# HMI_Features.net
KiCad netlist of a schematic drawn in Altium Designer
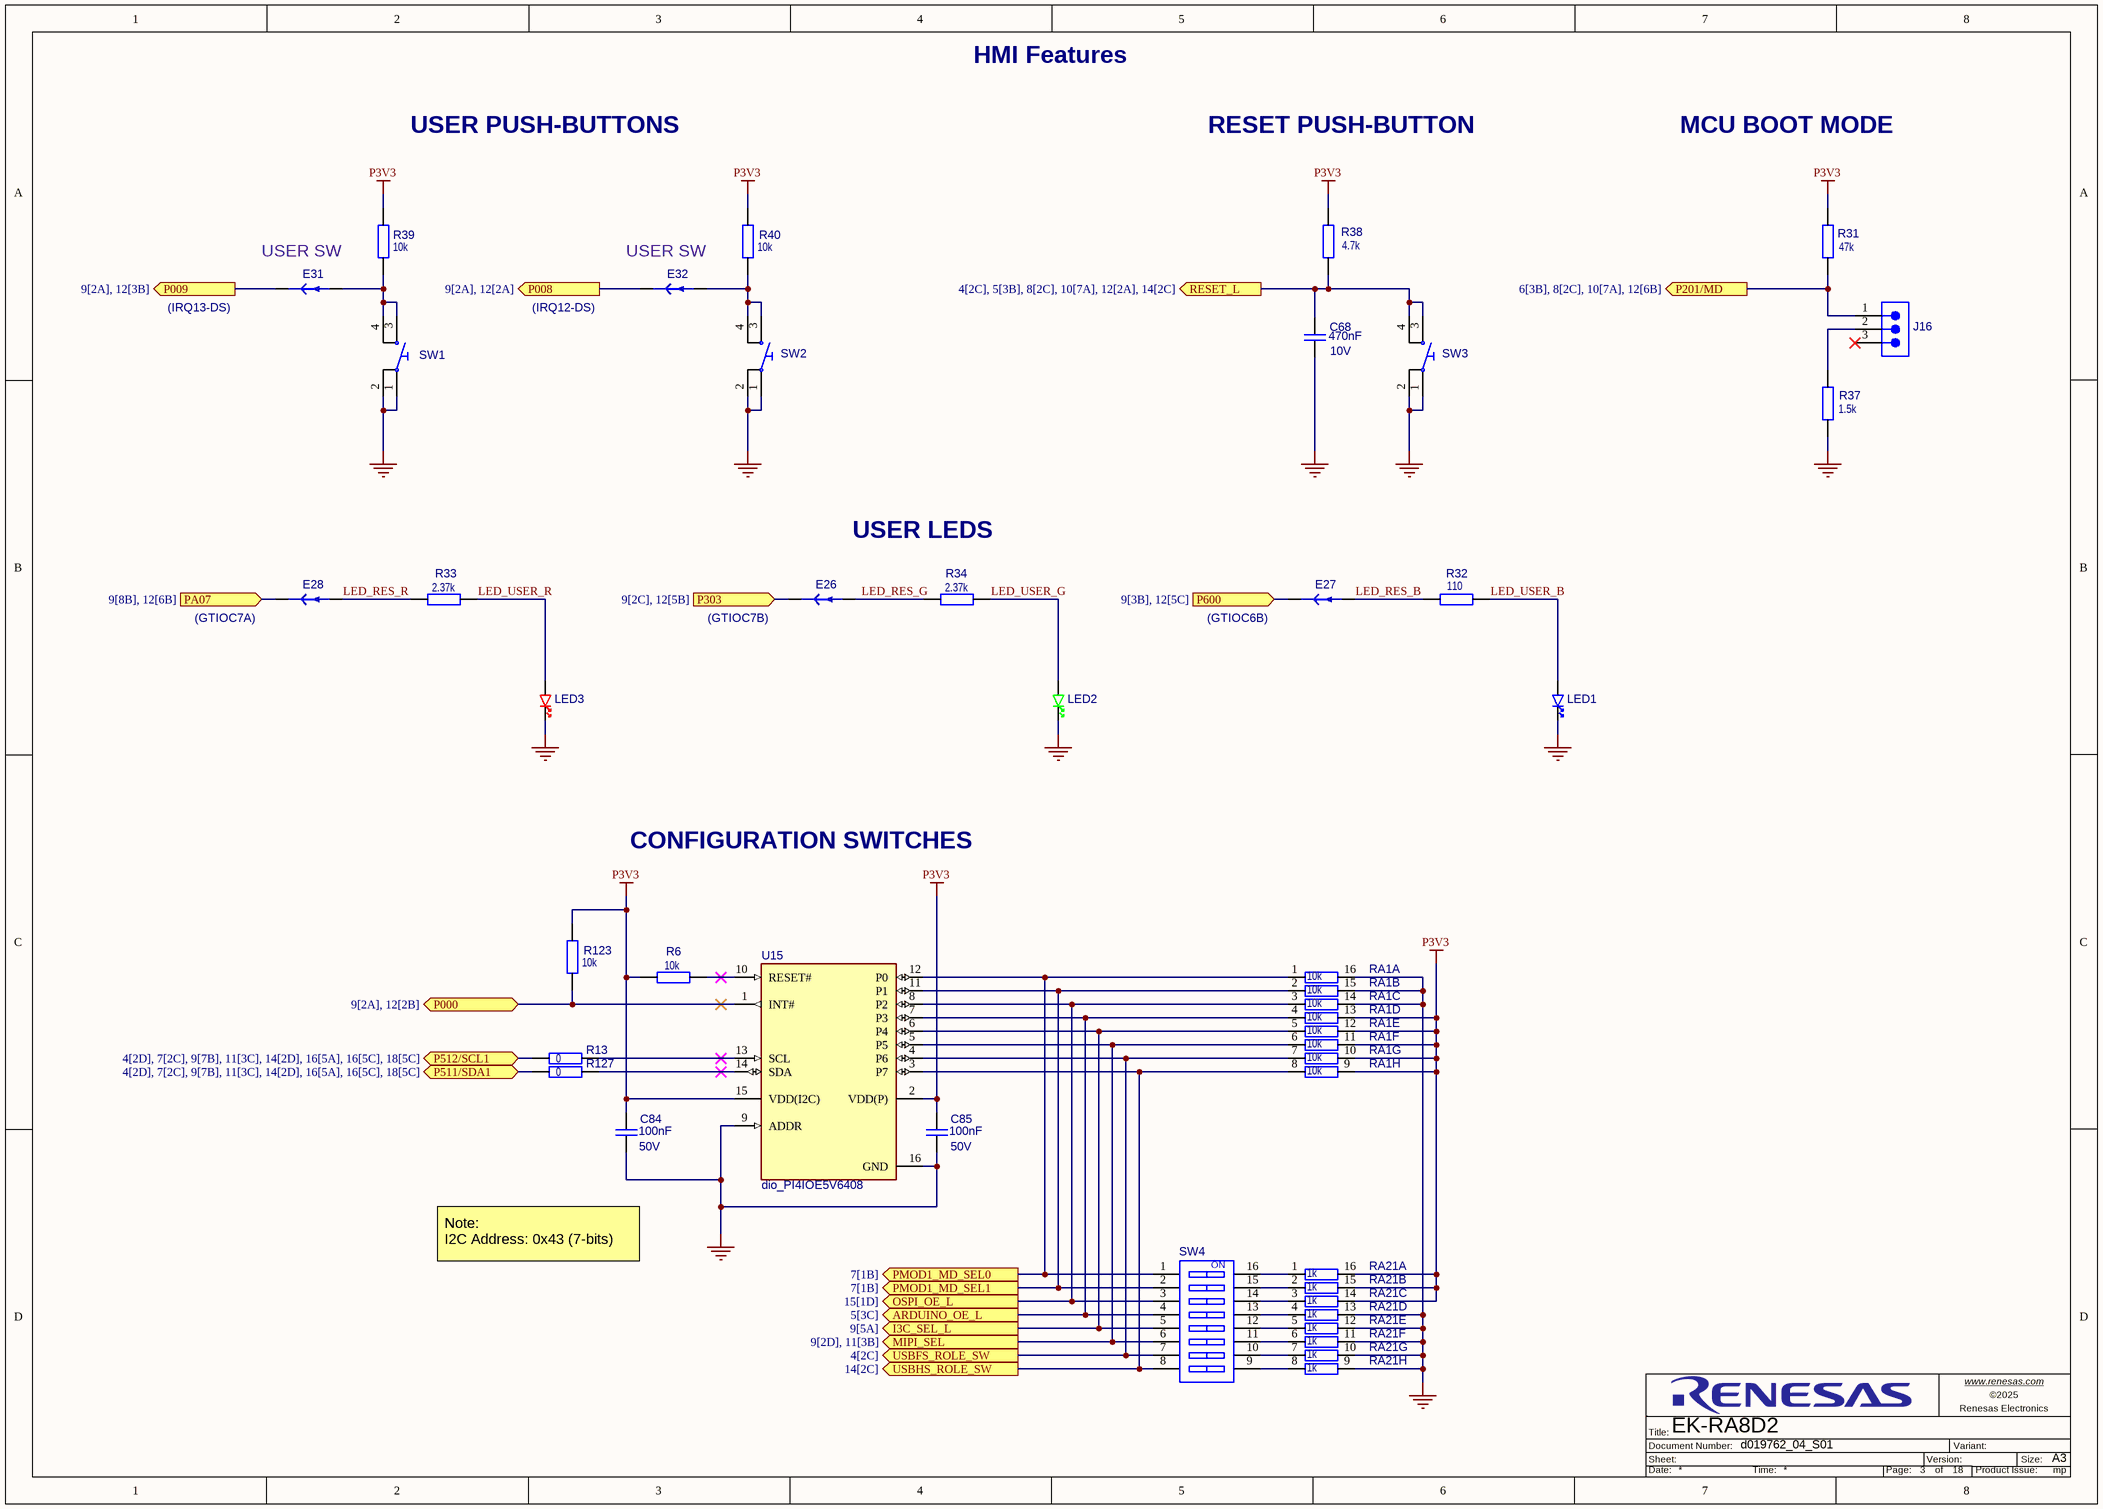
[diagram p0: HMI Features.SchDoc]

(export (version "E")
  (design (tool "Eeschema 10.0.6"))
  (components
    (comp (ref "C68")
      (value "470nF")
      (footprint "C_EIA0402_0p55")
      (description "Capacitor,EIA0402,470n,10V,X7R")
      (fields
        (field (name "TOLERANCE") "10%")
        (field (name "OPERATING VOLTAGE MAX") "10V")
        (field (name "Comment") "Capacitor")
      )
      (libsource (lib "ek-ra8d2_mp - Customer") (part "Capacitor"))
    )
    (comp (ref "C84")
      (value "100nF")
      (footprint "C_EIA0402_0p55")
      (description "Capacitor,EIA0402,100n,50V,X7R")
      (fields
        (field (name "TOLERANCE") "10%")
        (field (name "OPERATING VOLTAGE MAX") "50V")
        (field (name "Comment") "Capacitor")
      )
      (libsource (lib "ek-ra8d2_mp - Customer") (part "Capacitor"))
    )
    (comp (ref "C85")
      (value "100nF")
      (footprint "C_EIA0402_0p55")
      (description "Capacitor,EIA0402,100n,50V,X7R")
      (fields
        (field (name "TOLERANCE") "10%")
        (field (name "OPERATING VOLTAGE MAX") "50V")
        (field (name "Comment") "Capacitor")
      )
      (libsource (lib "ek-ra8d2_mp - Customer") (part "Capacitor"))
    )
    (comp (ref "E26")
      (value "TRACE_CUT_0805")
      (footprint "trace_cut_0805")
      (description "Trace Cut, SMD, 0805 size")
      (libsource (lib "ek-ra8d2_mp - Customer") (part "trace_cut"))
    )
    (comp (ref "E27")
      (value "TRACE_CUT_0805")
      (footprint "trace_cut_0805")
      (description "Trace Cut, SMD, 0805 size")
      (libsource (lib "ek-ra8d2_mp - Customer") (part "trace_cut"))
    )
    (comp (ref "E28")
      (value "TRACE_CUT_0805")
      (footprint "trace_cut_0805")
      (description "Trace Cut, SMD, 0805 size")
      (libsource (lib "ek-ra8d2_mp - Customer") (part "trace_cut"))
    )
    (comp (ref "E31")
      (value "TRACE_CUT_0805")
      (footprint "trace_cut_0805")
      (description "Trace Cut, SMD, 0805 size")
      (libsource (lib "ek-ra8d2_mp - Customer") (part "trace_cut"))
    )
    (comp (ref "E32")
      (value "TRACE_CUT_0805")
      (footprint "trace_cut_0805")
      (description "Trace Cut, SMD, 0805 size")
      (libsource (lib "ek-ra8d2_mp - Customer") (part "trace_cut"))
    )
    (comp (ref "J16")
      (value "2842102-3")
      (footprint "tec_2842102-3")
      (description "Header, 3way, 1row, vertical, 2.00mm, SMD")
      (libsource (lib "ek-ra8d2_mp - Customer") (part "CON_003"))
    )
    (comp (ref "LED1")
      (value "150060BS75000")
      (footprint "led_0603_b")
      (description "Standard LEDs - SMD Blue, 470nm 90 to 145 mcd")
      (libsource (lib "ek-ra8d2_mp - Customer") (part "LED_blue"))
    )
    (comp (ref "LED2")
      (value "150060GS75000")
      (footprint "led_0603_g")
      (description "Standard LEDs - SMD Green, 525nm 220 to 430 mcd")
      (libsource (lib "ek-ra8d2_mp - Customer") (part "LED_green"))
    )
    (comp (ref "LED3")
      (value "150060RS75000")
      (footprint "led_0603_r")
      (description "Standard LEDs - SMD Red, 625nm 120 to 250 mcd")
      (libsource (lib "ek-ra8d2_mp - Customer") (part "LED_red"))
    )
    (comp (ref "R6")
      (value "10k")
      (footprint "R_EIA0402")
      (description "Resistor,EIA0402,10k,0.0625W")
      (fields (field (name "POWER") "62.5mW") (field (name "TOLERANCE") "1%"))
      (libsource (lib "") (part "Resistor_1"))
    )
    (comp (ref "R13")
      (value "0")
      (footprint "R_EIA0402")
      (description "Resistor,EIA0402,0,0.0625W")
      (fields (field (name "POWER") "62.5mW") (field (name "TOLERANCE") "5%"))
      (libsource (lib "") (part "Resistor_1"))
    )
    (comp (ref "R31")
      (value "47k")
      (footprint "R_EIA0402")
      (description "Resistor,EIA0402,47k,0.0625W")
      (fields (field (name "POWER") "62.5mW") (field (name "TOLERANCE") "1%"))
      (libsource (lib "ek-ra8d2_mp - Customer") (part "Resistor"))
    )
    (comp (ref "R32")
      (value "110")
      (footprint "R_EIA0402")
      (description "Resistor,EIA0402,110,0.0625W")
      (fields (field (name "POWER") "62.5mW") (field (name "TOLERANCE") "1%"))
      (libsource (lib "") (part "Resistor_2"))
    )
    (comp (ref "R33")
      (value "2.37k")
      (footprint "R_EIA0402")
      (description "Resistor,EIA0402,2.37k,0.0625W")
      (fields (field (name "POWER") "62.5mW") (field (name "TOLERANCE") "1%"))
      (libsource (lib "") (part "Resistor_2"))
    )
    (comp (ref "R34")
      (value "2.37k")
      (footprint "R_EIA0402")
      (description "Resistor,EIA0402,2.37k,0.0625W")
      (fields (field (name "POWER") "62.5mW") (field (name "TOLERANCE") "1%"))
      (libsource (lib "") (part "Resistor_2"))
    )
    (comp (ref "R37")
      (value "1.5k")
      (footprint "R_EIA0402")
      (description "Resistor,EIA0402,1.5k,0.0625W")
      (fields (field (name "POWER") "62.5mW") (field (name "TOLERANCE") "1%"))
      (libsource (lib "ek-ra8d2_mp - Customer") (part "Resistor"))
    )
    (comp (ref "R38")
      (value "4.7k")
      (footprint "R_EIA0402")
      (description "Resistor,EIA0402,4.7k,0.0625W")
      (fields (field (name "POWER") "62.5mW") (field (name "TOLERANCE") "1%"))
      (libsource (lib "ek-ra8d2_mp - Customer") (part "Resistor"))
    )
    (comp (ref "R39")
      (value "10k")
      (footprint "R_EIA0402")
      (description "Resistor,EIA0402,10k,0.0625W")
      (fields (field (name "POWER") "62.5mW") (field (name "TOLERANCE") "1%"))
      (libsource (lib "ek-ra8d2_mp - Customer") (part "Resistor"))
    )
    (comp (ref "R40")
      (value "10k")
      (footprint "R_EIA0402")
      (description "Resistor,EIA0402,10k,0.0625W")
      (fields (field (name "POWER") "62.5mW") (field (name "TOLERANCE") "1%"))
      (libsource (lib "ek-ra8d2_mp - Customer") (part "Resistor"))
    )
    (comp (ref "R123")
      (value "10k")
      (footprint "R_EIA0402")
      (description "Resistor,EIA0402,10k,0.0625W")
      (fields (field (name "POWER") "62.5mW") (field (name "TOLERANCE") "1%"))
      (libsource (lib "ek-ra8d2_mp - Customer") (part "Resistor"))
    )
    (comp (ref "R127")
      (value "0")
      (footprint "R_EIA0402")
      (description "Resistor,EIA0402,0,0.0625W")
      (fields (field (name "POWER") "62.5mW") (field (name "TOLERANCE") "5%"))
      (libsource (lib "") (part "Resistor_1"))
    )
    (comp (ref "RA1")
      (value "10k")
      (footprint "R_Array_EIA1506")
      (description "Resistor Network & Array,EIA1506,10k,0.063W")
      (fields (field (name "TOLERANCE") "5%") (field (name "POWER") "62.5mW"))
      (libsource (lib "ek-ra8d2_mp - Customer") (part "Resistor_Array_16-Leads"))
    )
    (comp (ref "RA21")
      (value "1k")
      (footprint "R_Array_EIA1506")
      (fields
        (field (name "POWER") "63mW")
        (field (name "TOLERANCE") "5%")
        (field (name "Comment") "EXB-2HV102JV")
      )
      (libsource (lib "ek-ra8d2_mp - Customer") (part "Resistor_Array_16-Leads"))
    )
    (comp (ref "SW1")
      (value "PTS645SM43SMTR92LFS")
      (footprint "ck_PTS645_g_smt_4p3")
      (description "SMD Push Button Switch, 4-pin, 6x6mm, 4.3mm height, Blue Actuator")
      (libsource (lib "ek-ra8d2_mp - Customer") (part "TACT_4Pin"))
    )
    (comp (ref "SW2")
      (value "PTS645SM43SMTR92LFS")
      (footprint "ck_PTS645_g_smt_4p3")
      (description "SMD Push Button Switch, 4-pin, 6x6mm, 4.3mm height, Blue Actuator")
      (libsource (lib "ek-ra8d2_mp - Customer") (part "TACT_4Pin"))
    )
    (comp (ref "SW3")
      (value "PTS645SK43SMTR92LFS")
      (footprint "ck_PTS645_g_smt_4p3_red")
      (description "SMD Push Button Switch, 4-pin, 6x6mm, 4.3mm height,  Red Actuator")
      (libsource (lib "ek-ra8d2_mp - Customer") (part "TACT_4Pin"))
    )
    (comp (ref "SW4")
      (value "416131160808")
      (footprint "wue_416131160808")
      (description "WS-DISV Small Compact SMT Flat Actuator with Top Tape 1.27 mm")
      (libsource (lib "ek-ra8d2_mp - Customer") (part "DIP-08"))
    )
    (comp (ref "U15")
      (value "dio_PI4IOE5V6408")
      (footprint "dio_uqfn-16_zta16")
      (description "Low-voltage translating 8-bit I2C-bus I/O Expander")
      (libsource (lib "ek-ra8d2_mp - Customer") (part "dio_PI4IOE5V6408"))
    )
  )
  (nets
    (net (code "1") (name "/ARDUINO_OE_L") (class "Default")
      (node (ref "RA1") (pin "4") (pinfunction "4_4") (pintype "passive"))
      (node (ref "SW4") (pin "4") (pinfunction "4_4") (pintype "passive"))
      (node (ref "U15") (pin "7") (pinfunction "P3_7") (pintype "bidirectional"))
    )
    (net (code "2") (name "/I3C_SEL_L") (class "Default")
      (node (ref "RA1") (pin "5") (pinfunction "5_5") (pintype "passive"))
      (node (ref "SW4") (pin "5") (pinfunction "5_5") (pintype "passive"))
      (node (ref "U15") (pin "6") (pinfunction "P4_6") (pintype "bidirectional"))
    )
    (net (code "3") (name "/LED_RES_B") (class "Default")
      (node (ref "E27") (pin "2") (pinfunction "2_2") (pintype "passive"))
      (node (ref "R32") (pin "1") (pinfunction "1_1") (pintype "passive"))
    )
    (net (code "4") (name "/LED_RES_G") (class "Default")
      (node (ref "E26") (pin "2") (pinfunction "2_2") (pintype "passive"))
      (node (ref "R34") (pin "1") (pinfunction "1_1") (pintype "passive"))
    )
    (net (code "5") (name "/LED_RES_R") (class "Default")
      (node (ref "E28") (pin "2") (pinfunction "2_2") (pintype "passive"))
      (node (ref "R33") (pin "1") (pinfunction "1_1") (pintype "passive"))
    )
    (net (code "6") (name "/LED_USER_B") (class "Default")
      (node (ref "LED1") (pin "2") (pinfunction "A_2") (pintype "passive"))
      (node (ref "R32") (pin "2") (pinfunction "2_2") (pintype "passive"))
    )
    (net (code "7") (name "/LED_USER_G") (class "Default")
      (node (ref "LED2") (pin "2") (pinfunction "A_2") (pintype "passive"))
      (node (ref "R34") (pin "2") (pinfunction "2_2") (pintype "passive"))
    )
    (net (code "8") (name "/LED_USER_R") (class "Default")
      (node (ref "LED3") (pin "2") (pinfunction "A_2") (pintype "passive"))
      (node (ref "R33") (pin "2") (pinfunction "2_2") (pintype "passive"))
    )
    (net (code "9") (name "/MIPI_SEL") (class "Default")
      (node (ref "RA1") (pin "6") (pinfunction "6_6") (pintype "passive"))
      (node (ref "SW4") (pin "6") (pinfunction "6_6") (pintype "passive"))
      (node (ref "U15") (pin "5") (pinfunction "P5_5") (pintype "bidirectional"))
    )
    (net (code "10") (name "/OSPI_OE_L") (class "Default")
      (node (ref "RA1") (pin "3") (pinfunction "3_3") (pintype "passive"))
      (node (ref "SW4") (pin "3") (pinfunction "3_3") (pintype "passive"))
      (node (ref "U15") (pin "8") (pinfunction "P2_8") (pintype "bidirectional"))
    )
    (net (code "11") (name "/P000") (class "Default")
      (node (ref "R123") (pin "1") (pinfunction "1_1") (pintype "passive"))
      (node (ref "U15") (pin "1") (pinfunction "INT#_1") (pintype "output"))
    )
    (net (code "12") (name "/P008") (class "Default")
      (node (ref "E32") (pin "1") (pinfunction "1_1") (pintype "passive"))
    )
    (net (code "13") (name "/P009") (class "Default")
      (node (ref "E31") (pin "1") (pinfunction "1_1") (pintype "passive"))
    )
    (net (code "14") (name "/P201{slash}MD") (class "Default")
      (node (ref "J16") (pin "1") (pinfunction "1_1") (pintype "passive"))
      (node (ref "R31") (pin "1") (pinfunction "1_1") (pintype "passive"))
    )
    (net (code "15") (name "/P303") (class "Default")
      (node (ref "E26") (pin "1") (pinfunction "1_1") (pintype "passive"))
    )
    (net (code "16") (name "/P511{slash}SDA1") (class "Default")
      (node (ref "R127") (pin "2") (pinfunction "2_2") (pintype "passive"))
    )
    (net (code "17") (name "/P512{slash}SCL1") (class "Default")
      (node (ref "R13") (pin "2") (pinfunction "2_2") (pintype "passive"))
    )
    (net (code "18") (name "/P600") (class "Default")
      (node (ref "E27") (pin "1") (pinfunction "1_1") (pintype "passive"))
    )
    (net (code "19") (name "/PA07") (class "Default")
      (node (ref "E28") (pin "1") (pinfunction "1_1") (pintype "passive"))
    )
    (net (code "20") (name "/PMOD1_MD_SEL0") (class "Default")
      (node (ref "RA1") (pin "1") (pinfunction "1_1") (pintype "passive"))
      (node (ref "SW4") (pin "1") (pinfunction "1_1") (pintype "passive"))
      (node (ref "U15") (pin "12") (pinfunction "P0_12") (pintype "bidirectional"))
    )
    (net (code "21") (name "/PMOD1_MD_SEL1") (class "Default")
      (node (ref "RA1") (pin "2") (pinfunction "2_2") (pintype "passive"))
      (node (ref "SW4") (pin "2") (pinfunction "2_2") (pintype "passive"))
      (node (ref "U15") (pin "11") (pinfunction "P1_11") (pintype "bidirectional"))
    )
    (net (code "22") (name "/RESET_L") (class "Default")
      (node (ref "C68") (pin "2") (pinfunction "2_2") (pintype "passive"))
      (node (ref "R38") (pin "1") (pinfunction "1_1") (pintype "passive"))
      (node (ref "SW3") (pin "3") (pinfunction "3_3") (pintype "passive"))
      (node (ref "SW3") (pin "4") (pinfunction "4_4") (pintype "passive"))
    )
    (net (code "23") (name "/USBFS_ROLE_SW") (class "Default")
      (node (ref "RA1") (pin "7") (pinfunction "7_7") (pintype "passive"))
      (node (ref "SW4") (pin "7") (pinfunction "7_7") (pintype "passive"))
      (node (ref "U15") (pin "4") (pinfunction "P6_4") (pintype "bidirectional"))
    )
    (net (code "24") (name "/USBHS_ROLE_SW") (class "Default")
      (node (ref "RA1") (pin "8") (pinfunction "8_8") (pintype "passive"))
      (node (ref "SW4") (pin "8") (pinfunction "8_8") (pintype "passive"))
      (node (ref "U15") (pin "3") (pinfunction "P7_3") (pintype "bidirectional"))
    )
    (net (code "25") (name "GND") (class "Default")
      (node (ref "C68") (pin "1") (pinfunction "1_1") (pintype "passive"))
      (node (ref "C84") (pin "1") (pinfunction "1_1") (pintype "passive"))
      (node (ref "C85") (pin "1") (pinfunction "1_1") (pintype "passive"))
      (node (ref "LED1") (pin "1") (pinfunction "K_1") (pintype "passive"))
      (node (ref "LED2") (pin "1") (pinfunction "K_1") (pintype "passive"))
      (node (ref "LED3") (pin "1") (pinfunction "K_1") (pintype "passive"))
      (node (ref "R37") (pin "1") (pinfunction "1_1") (pintype "passive"))
      (node (ref "RA1") (pin "14") (pinfunction "14_14") (pintype "passive"))
      (node (ref "RA1") (pin "15") (pinfunction "15_15") (pintype "passive"))
      (node (ref "RA1") (pin "16") (pinfunction "16_16") (pintype "passive"))
      (node (ref "RA21") (pin "10") (pinfunction "10_10") (pintype "passive"))
      (node (ref "RA21") (pin "11") (pinfunction "11_11") (pintype "passive"))
      (node (ref "RA21") (pin "12") (pinfunction "12_12") (pintype "passive"))
      (node (ref "RA21") (pin "13") (pinfunction "13_13") (pintype "passive"))
      (node (ref "RA21") (pin "9") (pinfunction "9_9") (pintype "passive"))
      (node (ref "SW1") (pin "1") (pinfunction "1_1") (pintype "passive"))
      (node (ref "SW1") (pin "2") (pinfunction "2_2") (pintype "passive"))
      (node (ref "SW2") (pin "1") (pinfunction "1_1") (pintype "passive"))
      (node (ref "SW2") (pin "2") (pinfunction "2_2") (pintype "passive"))
      (node (ref "SW3") (pin "1") (pinfunction "1_1") (pintype "passive"))
      (node (ref "SW3") (pin "2") (pinfunction "2_2") (pintype "passive"))
      (node (ref "U15") (pin "16") (pinfunction "GND_16") (pintype "power_in"))
      (node (ref "U15") (pin "9") (pinfunction "ADDR_9") (pintype "input"))
    )
    (net (code "26") (name "Net-(E31-Pad2)") (class "Default")
      (node (ref "E31") (pin "2") (pinfunction "2_2") (pintype "passive"))
      (node (ref "R39") (pin "1") (pinfunction "1_1") (pintype "passive"))
      (node (ref "SW1") (pin "3") (pinfunction "3_3") (pintype "passive"))
      (node (ref "SW1") (pin "4") (pinfunction "4_4") (pintype "passive"))
    )
    (net (code "27") (name "Net-(E32-Pad2)") (class "Default")
      (node (ref "E32") (pin "2") (pinfunction "2_2") (pintype "passive"))
      (node (ref "R40") (pin "1") (pinfunction "1_1") (pintype "passive"))
      (node (ref "SW2") (pin "3") (pinfunction "3_3") (pintype "passive"))
      (node (ref "SW2") (pin "4") (pinfunction "4_4") (pintype "passive"))
    )
    (net (code "28") (name "Net-(J16-Pad2)") (class "Default")
      (node (ref "J16") (pin "2") (pinfunction "2_2") (pintype "passive"))
      (node (ref "R37") (pin "2") (pinfunction "2_2") (pintype "passive"))
    )
    (net (code "29") (name "Net-(RA21-Pad1)") (class "Default")
      (node (ref "RA21") (pin "1") (pinfunction "1_1") (pintype "passive"))
      (node (ref "SW4") (pin "16") (pinfunction "16_16") (pintype "passive"))
    )
    (net (code "30") (name "Net-(RA21-Pad2)") (class "Default")
      (node (ref "RA21") (pin "2") (pinfunction "2_2") (pintype "passive"))
      (node (ref "SW4") (pin "15") (pinfunction "15_15") (pintype "passive"))
    )
    (net (code "31") (name "Net-(RA21-Pad3)") (class "Default")
      (node (ref "RA21") (pin "3") (pinfunction "3_3") (pintype "passive"))
      (node (ref "SW4") (pin "14") (pinfunction "14_14") (pintype "passive"))
    )
    (net (code "32") (name "Net-(RA21-Pad4)") (class "Default")
      (node (ref "RA21") (pin "4") (pinfunction "4_4") (pintype "passive"))
      (node (ref "SW4") (pin "13") (pinfunction "13_13") (pintype "passive"))
    )
    (net (code "33") (name "Net-(RA21-Pad5)") (class "Default")
      (node (ref "RA21") (pin "5") (pinfunction "5_5") (pintype "passive"))
      (node (ref "SW4") (pin "12") (pinfunction "12_12") (pintype "passive"))
    )
    (net (code "34") (name "Net-(RA21-Pad6)") (class "Default")
      (node (ref "RA21") (pin "6") (pinfunction "6_6") (pintype "passive"))
      (node (ref "SW4") (pin "11") (pinfunction "11_11") (pintype "passive"))
    )
    (net (code "35") (name "Net-(RA21-Pad7)") (class "Default")
      (node (ref "RA21") (pin "7") (pinfunction "7_7") (pintype "passive"))
      (node (ref "SW4") (pin "10") (pinfunction "10_10") (pintype "passive"))
    )
    (net (code "36") (name "Net-(RA21-Pad8)") (class "Default")
      (node (ref "RA21") (pin "8") (pinfunction "8_8") (pintype "passive"))
      (node (ref "SW4") (pin "9") (pinfunction "9_9") (pintype "passive"))
    )
    (net (code "37") (name "Net-(U15-RESET#)") (class "Default")
      (node (ref "R6") (pin "1") (pinfunction "1_1") (pintype "passive"))
      (node (ref "U15") (pin "10") (pinfunction "RESET#_10") (pintype "input"))
    )
    (net (code "38") (name "Net-(U15-SCL)") (class "Default")
      (node (ref "R13") (pin "1") (pinfunction "1_1") (pintype "passive"))
      (node (ref "U15") (pin "13") (pinfunction "SCL_13") (pintype "input"))
    )
    (net (code "39") (name "Net-(U15-SDA)") (class "Default")
      (node (ref "R127") (pin "1") (pinfunction "1_1") (pintype "passive"))
      (node (ref "U15") (pin "14") (pinfunction "SDA_14") (pintype "bidirectional"))
    )
    (net (code "40") (name "P3V3") (class "Default")
      (node (ref "C84") (pin "2") (pinfunction "2_2") (pintype "passive"))
      (node (ref "C85") (pin "2") (pinfunction "2_2") (pintype "passive"))
      (node (ref "R123") (pin "2") (pinfunction "2_2") (pintype "passive"))
      (node (ref "R31") (pin "2") (pinfunction "2_2") (pintype "passive"))
      (node (ref "R38") (pin "2") (pinfunction "2_2") (pintype "passive"))
      (node (ref "R39") (pin "2") (pinfunction "2_2") (pintype "passive"))
      (node (ref "R40") (pin "2") (pinfunction "2_2") (pintype "passive"))
      (node (ref "R6") (pin "2") (pinfunction "2_2") (pintype "passive"))
      (node (ref "RA1") (pin "10") (pinfunction "10_10") (pintype "passive"))
      (node (ref "RA1") (pin "11") (pinfunction "11_11") (pintype "passive"))
      (node (ref "RA1") (pin "12") (pinfunction "12_12") (pintype "passive"))
      (node (ref "RA1") (pin "13") (pinfunction "13_13") (pintype "passive"))
      (node (ref "RA1") (pin "9") (pinfunction "9_9") (pintype "passive"))
      (node (ref "RA21") (pin "14") (pinfunction "14_14") (pintype "passive"))
      (node (ref "RA21") (pin "15") (pinfunction "15_15") (pintype "passive"))
      (node (ref "RA21") (pin "16") (pinfunction "16_16") (pintype "passive"))
      (node (ref "U15") (pin "15") (pinfunction "VDD(I2C)_15") (pintype "power_in"))
      (node (ref "U15") (pin "2") (pinfunction "VDD(P)_2") (pintype "power_in"))
    )
    (net (code "41") (name "unconnected-(J16-Pad3)") (class "Default")
      (node (ref "J16") (pin "3") (pinfunction "3_3") (pintype "passive+no_connect"))
    )
  )
)
